# Driver.net
KiCad netlist of a schematic drawn in Altium Designer
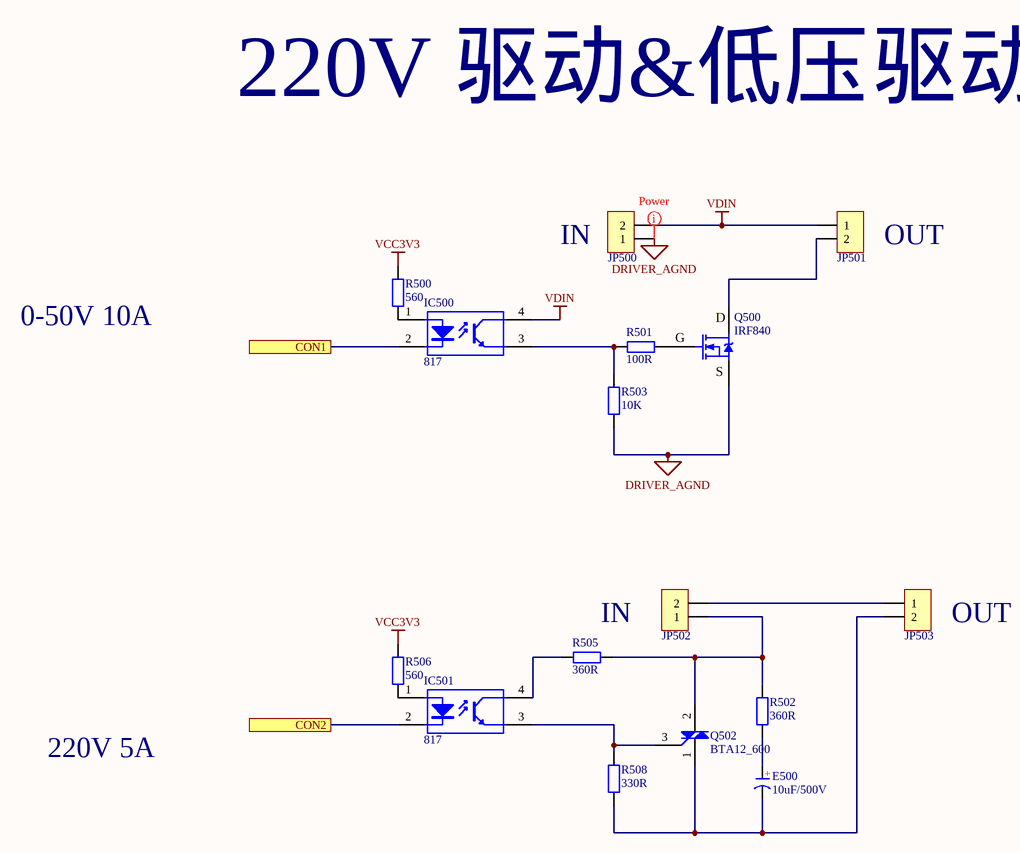
[diagram p0: Driver.SchDoc]

(export (version "E")
  (design (tool "Eeschema 10.0.6"))
  (components
    (comp (ref "E500")
      (value "10uF/500V")
      (footprint "CS 2.0*5*8 - R")
      (description "直插固态电容")
      (fields (field (name "版权归属") "源创客"))
      (libsource (lib "3.1   - 电阻-电容-电感") (part "C-CS"))
    )
    (comp (ref "IC500")
      (value "817")
      (footprint "DIP4-300")
      (description "线性光耦")
      (fields (field (name "版权归属") "源创客"))
      (libsource (lib "11.1 - 传感元件") (part "817"))
    )
    (comp (ref "IC501")
      (value "817")
      (footprint "DIP4-300")
      (description "线性光耦")
      (fields (field (name "版权归属") "源创客"))
      (libsource (lib "11.1 - 传感元件") (part "817"))
    )
    (comp (ref "JP500")
      (value "HDR-1X2")
      (footprint "KF2EDGK5.0-LI-2P")
      (description "2P接插件")
      (fields (field (name "版权归属") "源创客"))
      (libsource (lib "") (part "Header 2_1"))
    )
    (comp (ref "JP501")
      (value "HDR-1X2")
      (footprint "KF2EDGK5.0-LI-2P")
      (description "2P接插件")
      (fields (field (name "版权归属") "源创客"))
      (libsource (lib "4.9   - 接插件-脚距5.0") (part "Header 2"))
    )
    (comp (ref "JP502")
      (value "HDR-1X2")
      (footprint "KF2EDGK5.0-LI-2P")
      (description "2P接插件")
      (fields (field (name "版权归属") "源创客"))
      (libsource (lib "") (part "Header 2_1"))
    )
    (comp (ref "JP503")
      (value "HDR-1X2")
      (footprint "KF2EDGK5.0-LI-2P")
      (description "2P接插件")
      (fields (field (name "版权归属") "源创客"))
      (libsource (lib "4.9   - 接插件-脚距5.0") (part "Header 2"))
    )
    (comp (ref "Q500")
      (value "IRF840")
      (footprint "TO220A")
      (description "N沟场效应管")
      (fields (field (name "版权归属") "源创客"))
      (libsource (lib "6.1   - 场效应管-可控硅") (part "IRF840"))
    )
    (comp (ref "Q502")
      (value "BTA12_600")
      (footprint "TO252")
      (description "双向可控硅")
      (fields (field (name "版权归属") "源创客"))
      (libsource (lib "6.1   - 场效应管-可控硅") (part "BTA12_600"))
    )
    (comp (ref "R500")
      (value "560")
      (footprint "R 0402_M")
      (description "贴片电阻")
      (fields (field (name "版权归属") "源创客"))
      (libsource (lib "3.1   - 电阻-电容-电感") (part "R"))
    )
    (comp (ref "R501")
      (value "100R")
      (footprint "R 0402_M")
      (description "贴片电阻")
      (fields (field (name "版权归属") "源创客"))
      (libsource (lib "3.1   - 电阻-电容-电感") (part "R"))
    )
    (comp (ref "R502")
      (value "360R")
      (footprint "R 0402_M")
      (description "贴片电阻")
      (fields (field (name "版权归属") "源创客"))
      (libsource (lib "3.1   - 电阻-电容-电感") (part "R"))
    )
    (comp (ref "R503")
      (value "10K")
      (footprint "R 0402_M")
      (description "贴片电阻")
      (fields (field (name "版权归属") "源创客"))
      (libsource (lib "3.1   - 电阻-电容-电感") (part "R"))
    )
    (comp (ref "R505")
      (value "360R")
      (footprint "R 0402_M")
      (description "贴片电阻")
      (fields (field (name "版权归属") "源创客"))
      (libsource (lib "3.1   - 电阻-电容-电感") (part "R"))
    )
    (comp (ref "R506")
      (value "560")
      (footprint "R 0402_M")
      (description "贴片电阻")
      (fields (field (name "版权归属") "源创客"))
      (libsource (lib "3.1   - 电阻-电容-电感") (part "R"))
    )
    (comp (ref "R508")
      (value "330R")
      (footprint "R 0402_M")
      (description "贴片电阻")
      (fields (field (name "版权归属") "源创客"))
      (libsource (lib "3.1   - 电阻-电容-电感") (part "R"))
    )
  )
  (nets
    (net (code "1") (name "/CON1") (class "Default")
      (node (ref "IC500") (pin "2") (pinfunction "K_2") (pintype "passive"))
    )
    (net (code "2") (name "/CON2") (class "Default")
      (node (ref "IC501") (pin "2") (pinfunction "K_2") (pintype "passive"))
    )
    (net (code "3") (name "DRIVER_AGND") (class "Default")
      (node (ref "JP500") (pin "1") (pinfunction "1_1") (pintype "passive"))
      (node (ref "Q500") (pin "3") (pinfunction "S_3") (pintype "passive"))
      (node (ref "R503") (pin "1") (pinfunction "1_1") (pintype "passive"))
    )
    (net (code "4") (name "Net-(E500-A)") (class "Default")
      (node (ref "E500") (pin "1") (pinfunction "A_1") (pintype "passive"))
      (node (ref "R502") (pin "2") (pinfunction "2_2") (pintype "passive"))
    )
    (net (code "5") (name "Net-(E500-K)") (class "Default")
      (node (ref "E500") (pin "2") (pinfunction "K_2") (pintype "passive"))
      (node (ref "JP503") (pin "2") (pinfunction "2_2") (pintype "passive"))
      (node (ref "Q502") (pin "1") (pinfunction "A1_1") (pintype "passive"))
      (node (ref "R508") (pin "1") (pinfunction "1_1") (pintype "passive"))
    )
    (net (code "6") (name "Net-(IC500-A)") (class "Default")
      (node (ref "IC500") (pin "1") (pinfunction "A_1") (pintype "passive"))
      (node (ref "R500") (pin "2") (pinfunction "2_2") (pintype "passive"))
    )
    (net (code "7") (name "Net-(IC500-E)") (class "Default")
      (node (ref "IC500") (pin "3") (pinfunction "E_3") (pintype "passive"))
      (node (ref "R501") (pin "1") (pinfunction "1_1") (pintype "passive"))
      (node (ref "R503") (pin "2") (pinfunction "2_2") (pintype "passive"))
    )
    (net (code "8") (name "Net-(IC501-A)") (class "Default")
      (node (ref "IC501") (pin "1") (pinfunction "A_1") (pintype "passive"))
      (node (ref "R506") (pin "2") (pinfunction "2_2") (pintype "passive"))
    )
    (net (code "9") (name "Net-(IC501-C)") (class "Default")
      (node (ref "IC501") (pin "4") (pinfunction "C_4") (pintype "passive"))
      (node (ref "R505") (pin "2") (pinfunction "2_2") (pintype "passive"))
    )
    (net (code "10") (name "Net-(IC501-E)") (class "Default")
      (node (ref "IC501") (pin "3") (pinfunction "E_3") (pintype "passive"))
      (node (ref "Q502") (pin "3") (pinfunction "G_3") (pintype "passive"))
      (node (ref "R508") (pin "2") (pinfunction "2_2") (pintype "passive"))
    )
    (net (code "11") (name "Net-(JP502-Pad2)") (class "Default")
      (node (ref "JP502") (pin "2") (pinfunction "2_2") (pintype "passive"))
      (node (ref "JP503") (pin "1") (pinfunction "1_1") (pintype "passive"))
    )
    (net (code "12") (name "Net-(Q500-D)") (class "Default")
      (node (ref "JP501") (pin "2") (pinfunction "2_2") (pintype "passive"))
      (node (ref "Q500") (pin "2") (pinfunction "D_2") (pintype "passive"))
    )
    (net (code "13") (name "Net-(Q500-G)") (class "Default")
      (node (ref "Q500") (pin "1") (pinfunction "G_1") (pintype "passive"))
      (node (ref "R501") (pin "2") (pinfunction "2_2") (pintype "passive"))
    )
    (net (code "14") (name "Net-(Q502-A2)") (class "Default")
      (node (ref "JP502") (pin "1") (pinfunction "1_1") (pintype "passive"))
      (node (ref "Q502") (pin "2") (pinfunction "A2_2") (pintype "passive"))
      (node (ref "R502") (pin "1") (pinfunction "1_1") (pintype "passive"))
      (node (ref "R505") (pin "1") (pinfunction "1_1") (pintype "passive"))
    )
    (net (code "15") (name "VCC3V3") (class "Default")
      (node (ref "R500") (pin "1") (pinfunction "1_1") (pintype "passive"))
      (node (ref "R506") (pin "1") (pinfunction "1_1") (pintype "passive"))
    )
    (net (code "16") (name "VDIN") (class "Default")
      (node (ref "IC500") (pin "4") (pinfunction "C_4") (pintype "passive"))
      (node (ref "JP500") (pin "2") (pinfunction "2_2") (pintype "passive"))
      (node (ref "JP501") (pin "1") (pinfunction "1_1") (pintype "passive"))
    )
  )
)
